# AMC_BOX_Panel.net
KiCad netlist of a schematic drawn in Altium Designer
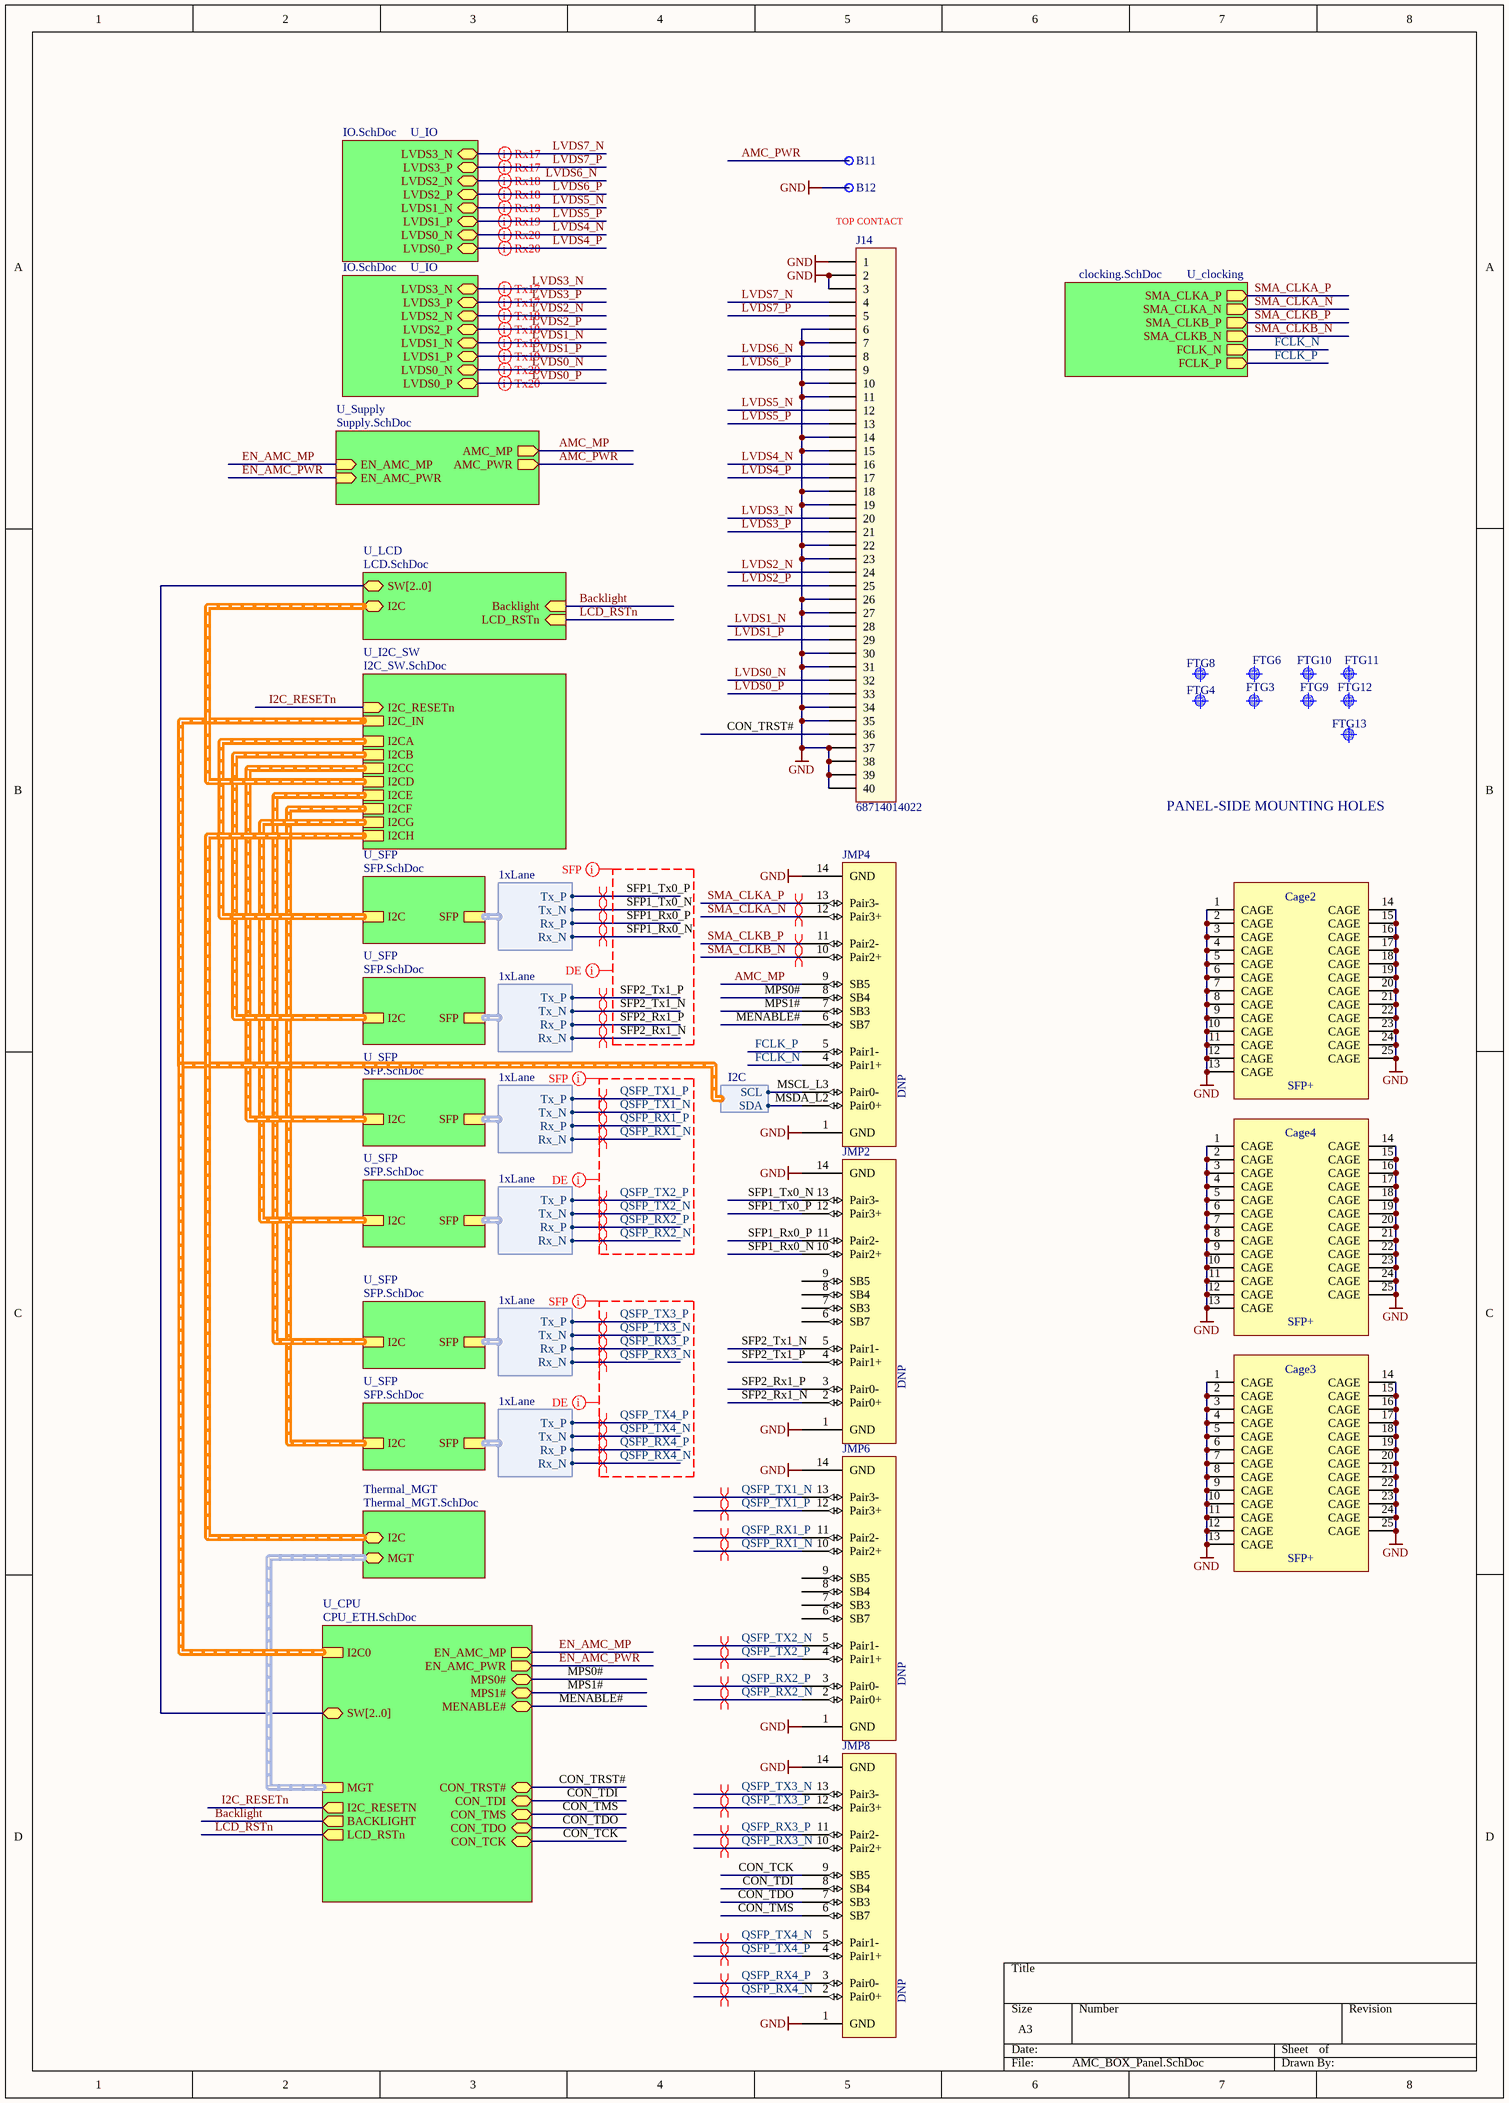
[diagram p0: AMC_BOX_Panel.SchDoc]

(export (version "E")
  (design (tool "Eeschema 10.0.6"))
  (components
    (comp (ref "B11")
      (value "Plated Hole")
      (footprint "c200h150")
      (description "Single Terminal Socket")
      (fields (field (name "PART NUMBER") "PLATED_HOLE1.5_PAD2.0") (field (name "AUTHOR") "CERN DEM JLC"))
      (libsource (lib "Eletro-mechanical") (part "Single Terminal Socket"))
    )
    (comp (ref "B12")
      (value "Plated Hole")
      (footprint "c200h150")
      (description "Single Terminal Socket")
      (fields (field (name "PART NUMBER") "PLATED_HOLE1.5_PAD2.0") (field (name "AUTHOR") "CERN DEM JLC"))
      (libsource (lib "Eletro-mechanical") (part "Single Terminal Socket"))
    )
    (comp (ref "Cage2")
      (value "SFP+")
      (footprint "TYCO_2007263-1")
      (description "SFP 1x2 Cage (25Pins)")
      (fields
        (field (name "PART NUMBER") "TYCO_2007263-1")
        (field (name "MANUFACTURER") "TYCO ELECTRONICS")
        (field (name "AUTHOR") "CERN DEM JLC")
      )
      (libsource (lib "Connectors") (part "SFP 1x2 Cage (25Pins)"))
    )
    (comp (ref "Cage3")
      (value "SFP+")
      (footprint "TYCO_2007263-1")
      (description "SFP 1x2 Cage (25Pins)")
      (fields
        (field (name "PART NUMBER") "TYCO_2007263-1")
        (field (name "MANUFACTURER") "TYCO ELECTRONICS")
        (field (name "AUTHOR") "CERN DEM JLC")
      )
      (libsource (lib "Connectors") (part "SFP 1x2 Cage (25Pins)"))
    )
    (comp (ref "Cage4")
      (value "SFP+")
      (footprint "TYCO_2007263-1")
      (description "SFP 1x2 Cage (25Pins)")
      (fields
        (field (name "PART NUMBER") "TYCO_2007263-1")
        (field (name "MANUFACTURER") "TYCO ELECTRONICS")
        (field (name "AUTHOR") "CERN DEM JLC")
      )
      (libsource (lib "Connectors") (part "SFP 1x2 Cage (25Pins)"))
    )
    (comp (ref "FTG3")
      (value "Use only in PCB")
      (footprint "FIDUCIAL_TOP_S100-200")
      (description "Fiducial Target")
      (fields (field (name "PART NUMBER") "FIDUCIAL_TARGET_S100-200") (field (name "AUTHOR") "CERN DEM JLC"))
      (libsource (lib "Eletro-mechanical") (part "Fiducial Target"))
    )
    (comp (ref "FTG4")
      (value "Use only in PCB")
      (footprint "FIDUCIAL_TOP_S100-200")
      (description "Fiducial Target")
      (fields (field (name "PART NUMBER") "FIDUCIAL_TARGET_S100-200") (field (name "AUTHOR") "CERN DEM JLC"))
      (libsource (lib "Eletro-mechanical") (part "Fiducial Target"))
    )
    (comp (ref "FTG6")
      (value "Use only in PCB")
      (footprint "FIDUCIAL_TOP_S100-200")
      (description "Fiducial Target")
      (fields (field (name "PART NUMBER") "FIDUCIAL_TARGET_S100-200") (field (name "AUTHOR") "CERN DEM JLC"))
      (libsource (lib "Eletro-mechanical") (part "Fiducial Target"))
    )
    (comp (ref "FTG8")
      (value "Use only in PCB")
      (footprint "FIDUCIAL_TOP_S100-200")
      (description "Fiducial Target")
      (fields (field (name "PART NUMBER") "FIDUCIAL_TARGET_S100-200") (field (name "AUTHOR") "CERN DEM JLC"))
      (libsource (lib "Eletro-mechanical") (part "Fiducial Target"))
    )
    (comp (ref "FTG9")
      (value "Use only in PCB")
      (footprint "FIDUCIAL_TOP_S100-200")
      (description "Fiducial Target")
      (fields (field (name "PART NUMBER") "FIDUCIAL_TARGET_S100-200") (field (name "AUTHOR") "CERN DEM JLC"))
      (libsource (lib "Eletro-mechanical") (part "Fiducial Target"))
    )
    (comp (ref "FTG10")
      (value "Use only in PCB")
      (footprint "FIDUCIAL_TOP_S100-200")
      (description "Fiducial Target")
      (fields (field (name "PART NUMBER") "FIDUCIAL_TARGET_S100-200") (field (name "AUTHOR") "CERN DEM JLC"))
      (libsource (lib "Eletro-mechanical") (part "Fiducial Target"))
    )
    (comp (ref "FTG11")
      (value "Use only in PCB")
      (footprint "FIDUCIAL_TOP_S100-200")
      (description "Fiducial Target")
      (fields (field (name "PART NUMBER") "FIDUCIAL_TARGET_S100-200") (field (name "AUTHOR") "CERN DEM JLC"))
      (libsource (lib "Eletro-mechanical") (part "Fiducial Target"))
    )
    (comp (ref "FTG12")
      (value "Use only in PCB")
      (footprint "FIDUCIAL_TOP_S100-200")
      (description "Fiducial Target")
      (fields (field (name "PART NUMBER") "FIDUCIAL_TARGET_S100-200") (field (name "AUTHOR") "CERN DEM JLC"))
      (libsource (lib "Eletro-mechanical") (part "Fiducial Target"))
    )
    (comp (ref "FTG13")
      (value "Use only in PCB")
      (footprint "FIDUCIAL_TOP_S100-200")
      (description "Fiducial Target")
      (fields (field (name "PART NUMBER") "FIDUCIAL_TARGET_S100-200") (field (name "AUTHOR") "CERN DEM JLC"))
      (libsource (lib "Eletro-mechanical") (part "Fiducial Target"))
    )
    (comp (ref "J14")
      (value "68714014022")
      (footprint "68714014022")
      (description "0.50 mm SMT ZIF Horizontal Top Contact WR-FPC, 40 pins")
      (fields (field (name "PUBLISHER") "Wurth Elektronik"))
      (libsource (lib "Altium_FPC_CONNECTORS (rev17a)") (part "68714014022"))
    )
    (comp (ref "JMP2")
      (value "DNP")
      (footprint "3M_Twinax_SL8801/12-10DA5-00")
      (libsource (lib "LIBRARY_SCH") (part "DNP"))
    )
    (comp (ref "JMP4")
      (value "DNP")
      (footprint "3M_Twinax_SL8801/12-10DA5-00")
      (libsource (lib "LIBRARY_SCH") (part "DNP"))
    )
    (comp (ref "JMP6")
      (value "DNP")
      (footprint "3M_Twinax_SL8801/12-10DA5-00")
      (libsource (lib "LIBRARY_SCH") (part "DNP"))
    )
    (comp (ref "JMP8")
      (value "DNP")
      (footprint "3M_Twinax_SL8801/12-10DA5-00")
      (libsource (lib "LIBRARY_SCH") (part "DNP"))
    )
  )
  (nets
    (net (code "3") (name "/AMC_MP") (class "Default")
      (node (ref "JMP4") (pin "9") (pinfunction "SB5_9") (pintype "bidirectional"))
    )
    (net (code "4") (name "/AMC_PWR") (class "Default")
      (node (ref "B11") (pin "1") (pinfunction "1_1") (pintype "bidirectional"))
    )
    (net (code "6") (name "/CON_TCK") (class "Default")
      (node (ref "JMP8") (pin "9") (pinfunction "SB5_9") (pintype "bidirectional"))
    )
    (net (code "7") (name "/CON_TDI") (class "Default")
      (node (ref "JMP8") (pin "8") (pinfunction "SB4_8") (pintype "bidirectional"))
    )
    (net (code "8") (name "/CON_TDO") (class "Default")
      (node (ref "JMP8") (pin "7") (pinfunction "SB3_7") (pintype "bidirectional"))
    )
    (net (code "9") (name "/CON_TMS") (class "Default")
      (node (ref "JMP8") (pin "6") (pinfunction "SB7_6") (pintype "bidirectional"))
    )
    (net (code "10") (name "/CON_TRST#") (class "Default")
      (node (ref "J14") (pin "36") (pinfunction "36_36") (pintype "passive"))
    )
    (net (code "13") (name "/FCLK_N") (class "Default")
      (node (ref "JMP4") (pin "4") (pinfunction "Pair1+_4") (pintype "bidirectional"))
    )
    (net (code "14") (name "/FCLK_P") (class "Default")
      (node (ref "JMP4") (pin "5") (pinfunction "Pair1-_5") (pintype "bidirectional"))
    )
    (net (code "25") (name "/LVDS0_N") (class "Default")
      (node (ref "J14") (pin "32") (pinfunction "32_32") (pintype "passive"))
    )
    (net (code "26") (name "/LVDS0_P") (class "Default")
      (node (ref "J14") (pin "33") (pinfunction "33_33") (pintype "passive"))
    )
    (net (code "27") (name "/LVDS1_N") (class "Default")
      (node (ref "J14") (pin "28") (pinfunction "28_28") (pintype "passive"))
    )
    (net (code "28") (name "/LVDS1_P") (class "Default")
      (node (ref "J14") (pin "29") (pinfunction "29_29") (pintype "passive"))
    )
    (net (code "29") (name "/LVDS2_N") (class "Default")
      (node (ref "J14") (pin "24") (pinfunction "24_24") (pintype "passive"))
    )
    (net (code "30") (name "/LVDS2_P") (class "Default")
      (node (ref "J14") (pin "25") (pinfunction "25_25") (pintype "passive"))
    )
    (net (code "31") (name "/LVDS3_N") (class "Default")
      (node (ref "J14") (pin "20") (pinfunction "20_20") (pintype "passive"))
    )
    (net (code "32") (name "/LVDS3_P") (class "Default")
      (node (ref "J14") (pin "21") (pinfunction "21_21") (pintype "passive"))
    )
    (net (code "33") (name "/LVDS4_N") (class "Default")
      (node (ref "J14") (pin "16") (pinfunction "16_16") (pintype "passive"))
    )
    (net (code "34") (name "/LVDS4_P") (class "Default")
      (node (ref "J14") (pin "17") (pinfunction "17_17") (pintype "passive"))
    )
    (net (code "35") (name "/LVDS5_N") (class "Default")
      (node (ref "J14") (pin "12") (pinfunction "12_12") (pintype "passive"))
    )
    (net (code "36") (name "/LVDS5_P") (class "Default")
      (node (ref "J14") (pin "13") (pinfunction "13_13") (pintype "passive"))
    )
    (net (code "37") (name "/LVDS6_N") (class "Default")
      (node (ref "J14") (pin "8") (pinfunction "8_8") (pintype "passive"))
    )
    (net (code "38") (name "/LVDS6_P") (class "Default")
      (node (ref "J14") (pin "9") (pinfunction "9_9") (pintype "passive"))
    )
    (net (code "39") (name "/LVDS7_N") (class "Default")
      (node (ref "J14") (pin "4") (pinfunction "4_4") (pintype "passive"))
    )
    (net (code "40") (name "/LVDS7_P") (class "Default")
      (node (ref "J14") (pin "5") (pinfunction "5_5") (pintype "passive"))
    )
    (net (code "41") (name "/MENABLE#") (class "Default")
      (node (ref "JMP4") (pin "6") (pinfunction "SB7_6") (pintype "bidirectional"))
    )
    (net (code "43") (name "/MPS0#") (class "Default")
      (node (ref "JMP4") (pin "8") (pinfunction "SB4_8") (pintype "bidirectional"))
    )
    (net (code "44") (name "/MPS1#") (class "Default")
      (node (ref "JMP4") (pin "7") (pinfunction "SB3_7") (pintype "bidirectional"))
    )
    (net (code "45") (name "/MSCL_L") (class "Default")
      (node (ref "JMP4") (pin "3") (pinfunction "Pair0-_3") (pintype "bidirectional"))
    )
    (net (code "46") (name "/MSDA_L") (class "Default")
      (node (ref "JMP4") (pin "2") (pinfunction "Pair0+_2") (pintype "bidirectional"))
    )
    (net (code "47") (name "/QSFP_RX1_N") (class "Default")
      (node (ref "JMP6") (pin "10") (pinfunction "Pair2+_10") (pintype "bidirectional"))
    )
    (net (code "48") (name "/QSFP_RX1_P") (class "Default")
      (node (ref "JMP6") (pin "11") (pinfunction "Pair2-_11") (pintype "bidirectional"))
    )
    (net (code "49") (name "/QSFP_RX2_N") (class "Default")
      (node (ref "JMP6") (pin "2") (pinfunction "Pair0+_2") (pintype "bidirectional"))
    )
    (net (code "50") (name "/QSFP_RX2_P") (class "Default")
      (node (ref "JMP6") (pin "3") (pinfunction "Pair0-_3") (pintype "bidirectional"))
    )
    (net (code "51") (name "/QSFP_RX3_N") (class "Default")
      (node (ref "JMP8") (pin "10") (pinfunction "Pair2+_10") (pintype "bidirectional"))
    )
    (net (code "52") (name "/QSFP_RX3_P") (class "Default")
      (node (ref "JMP8") (pin "11") (pinfunction "Pair2-_11") (pintype "bidirectional"))
    )
    (net (code "53") (name "/QSFP_RX4_N") (class "Default")
      (node (ref "JMP8") (pin "2") (pinfunction "Pair0+_2") (pintype "bidirectional"))
    )
    (net (code "54") (name "/QSFP_RX4_P") (class "Default")
      (node (ref "JMP8") (pin "3") (pinfunction "Pair0-_3") (pintype "bidirectional"))
    )
    (net (code "55") (name "/QSFP_TX1_N") (class "Default")
      (node (ref "JMP6") (pin "13") (pinfunction "Pair3-_13") (pintype "bidirectional"))
    )
    (net (code "56") (name "/QSFP_TX1_P") (class "Default")
      (node (ref "JMP6") (pin "12") (pinfunction "Pair3+_12") (pintype "bidirectional"))
    )
    (net (code "57") (name "/QSFP_TX2_N") (class "Default")
      (node (ref "JMP6") (pin "5") (pinfunction "Pair1-_5") (pintype "bidirectional"))
    )
    (net (code "58") (name "/QSFP_TX2_P") (class "Default")
      (node (ref "JMP6") (pin "4") (pinfunction "Pair1+_4") (pintype "bidirectional"))
    )
    (net (code "59") (name "/QSFP_TX3_N") (class "Default")
      (node (ref "JMP8") (pin "13") (pinfunction "Pair3-_13") (pintype "bidirectional"))
    )
    (net (code "60") (name "/QSFP_TX3_P") (class "Default")
      (node (ref "JMP8") (pin "12") (pinfunction "Pair3+_12") (pintype "bidirectional"))
    )
    (net (code "61") (name "/QSFP_TX4_N") (class "Default")
      (node (ref "JMP8") (pin "5") (pinfunction "Pair1-_5") (pintype "bidirectional"))
    )
    (net (code "62") (name "/QSFP_TX4_P") (class "Default")
      (node (ref "JMP8") (pin "4") (pinfunction "Pair1+_4") (pintype "bidirectional"))
    )
    (net (code "63") (name "/SFP1_Rx0_N") (class "Default")
      (node (ref "JMP2") (pin "10") (pinfunction "Pair2+_10") (pintype "bidirectional"))
    )
    (net (code "64") (name "/SFP1_Rx0_P") (class "Default")
      (node (ref "JMP2") (pin "11") (pinfunction "Pair2-_11") (pintype "bidirectional"))
    )
    (net (code "65") (name "/SFP1_Tx0_N") (class "Default")
      (node (ref "JMP2") (pin "13") (pinfunction "Pair3-_13") (pintype "bidirectional"))
    )
    (net (code "66") (name "/SFP1_Tx0_P") (class "Default")
      (node (ref "JMP2") (pin "12") (pinfunction "Pair3+_12") (pintype "bidirectional"))
    )
    (net (code "67") (name "/SFP2_Rx1_N") (class "Default")
      (node (ref "JMP2") (pin "2") (pinfunction "Pair0+_2") (pintype "bidirectional"))
    )
    (net (code "68") (name "/SFP2_Rx1_P") (class "Default")
      (node (ref "JMP2") (pin "3") (pinfunction "Pair0-_3") (pintype "bidirectional"))
    )
    (net (code "69") (name "/SFP2_Tx1_N") (class "Default")
      (node (ref "JMP2") (pin "5") (pinfunction "Pair1-_5") (pintype "bidirectional"))
    )
    (net (code "70") (name "/SFP2_Tx1_P") (class "Default")
      (node (ref "JMP2") (pin "4") (pinfunction "Pair1+_4") (pintype "bidirectional"))
    )
    (net (code "71") (name "/SMA_CLKA_N") (class "Default")
      (node (ref "JMP4") (pin "12") (pinfunction "Pair3+_12") (pintype "bidirectional"))
    )
    (net (code "72") (name "/SMA_CLKA_P") (class "Default")
      (node (ref "JMP4") (pin "13") (pinfunction "Pair3-_13") (pintype "bidirectional"))
    )
    (net (code "73") (name "/SMA_CLKB_N") (class "Default")
      (node (ref "JMP4") (pin "10") (pinfunction "Pair2+_10") (pintype "bidirectional"))
    )
    (net (code "74") (name "/SMA_CLKB_P") (class "Default")
      (node (ref "JMP4") (pin "11") (pinfunction "Pair2-_11") (pintype "bidirectional"))
    )
    (net (code "78") (name "GND") (class "Default")
      (node (ref "B12") (pin "1") (pinfunction "1_1") (pintype "bidirectional"))
      (node (ref "Cage2") (pin "1") (pinfunction "CAGE_1") (pintype "power_in"))
      (node (ref "Cage2") (pin "10") (pinfunction "CAGE_10") (pintype "power_in"))
      (node (ref "Cage2") (pin "11") (pinfunction "CAGE_11") (pintype "power_in"))
      (node (ref "Cage2") (pin "12") (pinfunction "CAGE_12") (pintype "power_in"))
      (node (ref "Cage2") (pin "13") (pinfunction "CAGE_13") (pintype "power_in"))
      (node (ref "Cage2") (pin "14") (pinfunction "CAGE_14") (pintype "power_in"))
      (node (ref "Cage2") (pin "15") (pinfunction "CAGE_15") (pintype "power_in"))
      (node (ref "Cage2") (pin "16") (pinfunction "CAGE_16") (pintype "power_in"))
      (node (ref "Cage2") (pin "17") (pinfunction "CAGE_17") (pintype "power_in"))
      (node (ref "Cage2") (pin "18") (pinfunction "CAGE_18") (pintype "power_in"))
      (node (ref "Cage2") (pin "19") (pinfunction "CAGE_19") (pintype "power_in"))
      (node (ref "Cage2") (pin "2") (pinfunction "CAGE_2") (pintype "power_in"))
      (node (ref "Cage2") (pin "20") (pinfunction "CAGE_20") (pintype "power_in"))
      (node (ref "Cage2") (pin "21") (pinfunction "CAGE_21") (pintype "power_in"))
      (node (ref "Cage2") (pin "22") (pinfunction "CAGE_22") (pintype "power_in"))
      (node (ref "Cage2") (pin "23") (pinfunction "CAGE_23") (pintype "power_in"))
      (node (ref "Cage2") (pin "24") (pinfunction "CAGE_24") (pintype "power_in"))
      (node (ref "Cage2") (pin "25") (pinfunction "CAGE_25") (pintype "power_in"))
      (node (ref "Cage2") (pin "3") (pinfunction "CAGE_3") (pintype "power_in"))
      (node (ref "Cage2") (pin "4") (pinfunction "CAGE_4") (pintype "power_in"))
      (node (ref "Cage2") (pin "5") (pinfunction "CAGE_5") (pintype "power_in"))
      (node (ref "Cage2") (pin "6") (pinfunction "CAGE_6") (pintype "power_in"))
      (node (ref "Cage2") (pin "7") (pinfunction "CAGE_7") (pintype "power_in"))
      (node (ref "Cage2") (pin "8") (pinfunction "CAGE_8") (pintype "power_in"))
      (node (ref "Cage2") (pin "9") (pinfunction "CAGE_9") (pintype "power_in"))
      (node (ref "Cage3") (pin "1") (pinfunction "CAGE_1") (pintype "power_in"))
      (node (ref "Cage3") (pin "10") (pinfunction "CAGE_10") (pintype "power_in"))
      (node (ref "Cage3") (pin "11") (pinfunction "CAGE_11") (pintype "power_in"))
      (node (ref "Cage3") (pin "12") (pinfunction "CAGE_12") (pintype "power_in"))
      (node (ref "Cage3") (pin "13") (pinfunction "CAGE_13") (pintype "power_in"))
      (node (ref "Cage3") (pin "14") (pinfunction "CAGE_14") (pintype "power_in"))
      (node (ref "Cage3") (pin "15") (pinfunction "CAGE_15") (pintype "power_in"))
      (node (ref "Cage3") (pin "16") (pinfunction "CAGE_16") (pintype "power_in"))
      (node (ref "Cage3") (pin "17") (pinfunction "CAGE_17") (pintype "power_in"))
      (node (ref "Cage3") (pin "18") (pinfunction "CAGE_18") (pintype "power_in"))
      (node (ref "Cage3") (pin "19") (pinfunction "CAGE_19") (pintype "power_in"))
      (node (ref "Cage3") (pin "2") (pinfunction "CAGE_2") (pintype "power_in"))
      (node (ref "Cage3") (pin "20") (pinfunction "CAGE_20") (pintype "power_in"))
      (node (ref "Cage3") (pin "21") (pinfunction "CAGE_21") (pintype "power_in"))
      (node (ref "Cage3") (pin "22") (pinfunction "CAGE_22") (pintype "power_in"))
      (node (ref "Cage3") (pin "23") (pinfunction "CAGE_23") (pintype "power_in"))
      (node (ref "Cage3") (pin "24") (pinfunction "CAGE_24") (pintype "power_in"))
      (node (ref "Cage3") (pin "25") (pinfunction "CAGE_25") (pintype "power_in"))
      (node (ref "Cage3") (pin "3") (pinfunction "CAGE_3") (pintype "power_in"))
      (node (ref "Cage3") (pin "4") (pinfunction "CAGE_4") (pintype "power_in"))
      (node (ref "Cage3") (pin "5") (pinfunction "CAGE_5") (pintype "power_in"))
      (node (ref "Cage3") (pin "6") (pinfunction "CAGE_6") (pintype "power_in"))
      (node (ref "Cage3") (pin "7") (pinfunction "CAGE_7") (pintype "power_in"))
      (node (ref "Cage3") (pin "8") (pinfunction "CAGE_8") (pintype "power_in"))
      (node (ref "Cage3") (pin "9") (pinfunction "CAGE_9") (pintype "power_in"))
      (node (ref "Cage4") (pin "1") (pinfunction "CAGE_1") (pintype "power_in"))
      (node (ref "Cage4") (pin "10") (pinfunction "CAGE_10") (pintype "power_in"))
      (node (ref "Cage4") (pin "11") (pinfunction "CAGE_11") (pintype "power_in"))
      (node (ref "Cage4") (pin "12") (pinfunction "CAGE_12") (pintype "power_in"))
      (node (ref "Cage4") (pin "13") (pinfunction "CAGE_13") (pintype "power_in"))
      (node (ref "Cage4") (pin "14") (pinfunction "CAGE_14") (pintype "power_in"))
      (node (ref "Cage4") (pin "15") (pinfunction "CAGE_15") (pintype "power_in"))
      (node (ref "Cage4") (pin "16") (pinfunction "CAGE_16") (pintype "power_in"))
      (node (ref "Cage4") (pin "17") (pinfunction "CAGE_17") (pintype "power_in"))
      (node (ref "Cage4") (pin "18") (pinfunction "CAGE_18") (pintype "power_in"))
      (node (ref "Cage4") (pin "19") (pinfunction "CAGE_19") (pintype "power_in"))
      (node (ref "Cage4") (pin "2") (pinfunction "CAGE_2") (pintype "power_in"))
      (node (ref "Cage4") (pin "20") (pinfunction "CAGE_20") (pintype "power_in"))
      (node (ref "Cage4") (pin "21") (pinfunction "CAGE_21") (pintype "power_in"))
      (node (ref "Cage4") (pin "22") (pinfunction "CAGE_22") (pintype "power_in"))
      (node (ref "Cage4") (pin "23") (pinfunction "CAGE_23") (pintype "power_in"))
      (node (ref "Cage4") (pin "24") (pinfunction "CAGE_24") (pintype "power_in"))
      (node (ref "Cage4") (pin "25") (pinfunction "CAGE_25") (pintype "power_in"))
      (node (ref "Cage4") (pin "3") (pinfunction "CAGE_3") (pintype "power_in"))
      (node (ref "Cage4") (pin "4") (pinfunction "CAGE_4") (pintype "power_in"))
      (node (ref "Cage4") (pin "5") (pinfunction "CAGE_5") (pintype "power_in"))
      (node (ref "Cage4") (pin "6") (pinfunction "CAGE_6") (pintype "power_in"))
      (node (ref "Cage4") (pin "7") (pinfunction "CAGE_7") (pintype "power_in"))
      (node (ref "Cage4") (pin "8") (pinfunction "CAGE_8") (pintype "power_in"))
      (node (ref "Cage4") (pin "9") (pinfunction "CAGE_9") (pintype "power_in"))
      (node (ref "J14") (pin "1") (pinfunction "1_1") (pintype "passive"))
      (node (ref "J14") (pin "10") (pinfunction "10_10") (pintype "passive"))
      (node (ref "J14") (pin "11") (pinfunction "11_11") (pintype "passive"))
      (node (ref "J14") (pin "14") (pinfunction "14_14") (pintype "passive"))
      (node (ref "J14") (pin "15") (pinfunction "15_15") (pintype "passive"))
      (node (ref "J14") (pin "18") (pinfunction "18_18") (pintype "passive"))
      (node (ref "J14") (pin "19") (pinfunction "19_19") (pintype "passive"))
      (node (ref "J14") (pin "2") (pinfunction "2_2") (pintype "passive"))
      (node (ref "J14") (pin "22") (pinfunction "22_22") (pintype "passive"))
      (node (ref "J14") (pin "23") (pinfunction "23_23") (pintype "passive"))
      (node (ref "J14") (pin "26") (pinfunction "26_26") (pintype "passive"))
      (node (ref "J14") (pin "27") (pinfunction "27_27") (pintype "passive"))
      (node (ref "J14") (pin "3") (pinfunction "3_3") (pintype "passive"))
      (node (ref "J14") (pin "30") (pinfunction "30_30") (pintype "passive"))
      (node (ref "J14") (pin "31") (pinfunction "31_31") (pintype "passive"))
      (node (ref "J14") (pin "34") (pinfunction "34_34") (pintype "passive"))
      (node (ref "J14") (pin "35") (pinfunction "35_35") (pintype "passive"))
      (node (ref "J14") (pin "37") (pinfunction "37_37") (pintype "passive"))
      (node (ref "J14") (pin "38") (pinfunction "38_38") (pintype "passive"))
      (node (ref "J14") (pin "39") (pinfunction "39_39") (pintype "passive"))
      (node (ref "J14") (pin "40") (pinfunction "40_40") (pintype "passive"))
      (node (ref "J14") (pin "6") (pinfunction "6_6") (pintype "passive"))
      (node (ref "J14") (pin "7") (pinfunction "7_7") (pintype "passive"))
      (node (ref "JMP2") (pin "1") (pinfunction "GND_1") (pintype "power_in"))
      (node (ref "JMP2") (pin "14") (pinfunction "GND_14") (pintype "power_in"))
      (node (ref "JMP4") (pin "1") (pinfunction "GND_1") (pintype "power_in"))
      (node (ref "JMP4") (pin "14") (pinfunction "GND_14") (pintype "power_in"))
      (node (ref "JMP6") (pin "1") (pinfunction "GND_1") (pintype "power_in"))
      (node (ref "JMP6") (pin "14") (pinfunction "GND_14") (pintype "power_in"))
      (node (ref "JMP8") (pin "1") (pinfunction "GND_1") (pintype "power_in"))
      (node (ref "JMP8") (pin "14") (pinfunction "GND_14") (pintype "power_in"))
    )
    (net (code "79") (name "unconnected-(JMP2-SB3-Pad7)") (class "Default")
      (node (ref "JMP2") (pin "7") (pinfunction "SB3_7") (pintype "bidirectional"))
    )
    (net (code "80") (name "unconnected-(JMP2-SB4-Pad8)") (class "Default")
      (node (ref "JMP2") (pin "8") (pinfunction "SB4_8") (pintype "bidirectional"))
    )
    (net (code "81") (name "unconnected-(JMP2-SB5-Pad9)") (class "Default")
      (node (ref "JMP2") (pin "9") (pinfunction "SB5_9") (pintype "bidirectional"))
    )
    (net (code "82") (name "unconnected-(JMP2-SB7-Pad6)") (class "Default")
      (node (ref "JMP2") (pin "6") (pinfunction "SB7_6") (pintype "bidirectional"))
    )
    (net (code "83") (name "unconnected-(JMP6-SB3-Pad7)") (class "Default")
      (node (ref "JMP6") (pin "7") (pinfunction "SB3_7") (pintype "bidirectional"))
    )
    (net (code "84") (name "unconnected-(JMP6-SB4-Pad8)") (class "Default")
      (node (ref "JMP6") (pin "8") (pinfunction "SB4_8") (pintype "bidirectional"))
    )
    (net (code "85") (name "unconnected-(JMP6-SB5-Pad9)") (class "Default")
      (node (ref "JMP6") (pin "9") (pinfunction "SB5_9") (pintype "bidirectional"))
    )
    (net (code "86") (name "unconnected-(JMP6-SB7-Pad6)") (class "Default")
      (node (ref "JMP6") (pin "6") (pinfunction "SB7_6") (pintype "bidirectional"))
    )
  )
)
